# tutorial.net
KiCad netlist of a schematic drawn in Altium Designer
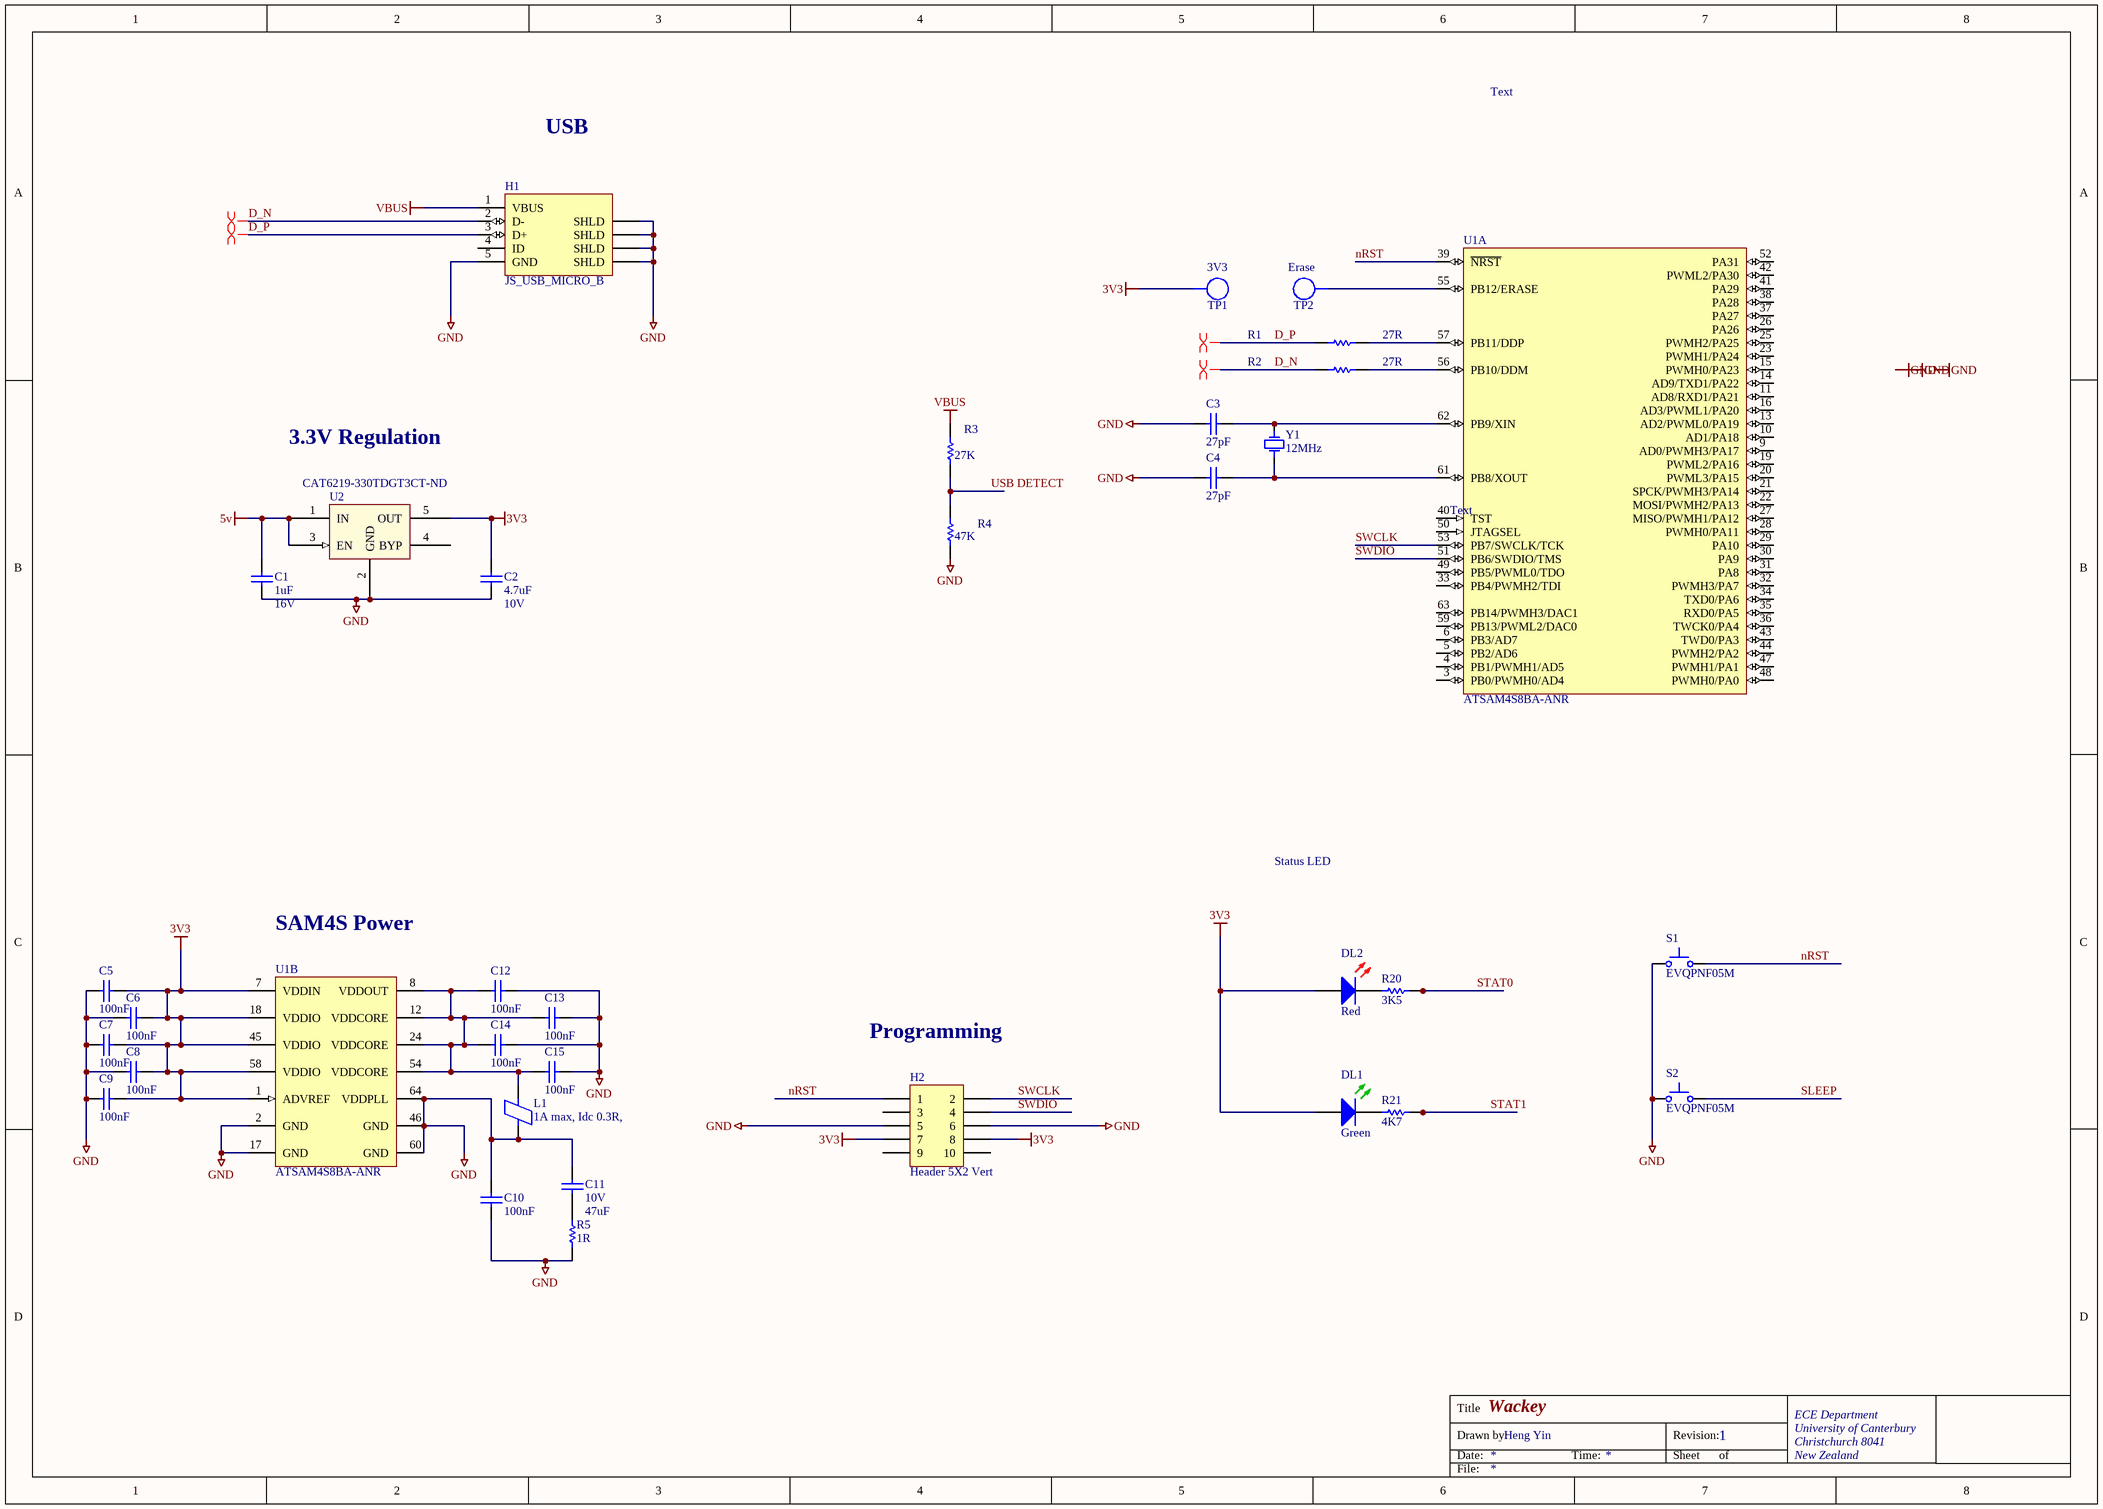
[diagram p0: tutorial.SchDoc]

(export (version "E")
  (design (tool "Eeschema 10.0.6"))
  (components
    (comp (ref "C1")
      (value "1uF")
      (footprint "CAPC1608L")
      (description "CAP CER 1uF Y5V -20% +80% 16V 0603")
      (fields (field (name "MAX VOLTAGE") "16V"))
      (libsource (lib "ECE AD19Components_22V1") (part "CC_1uF_0603"))
    )
    (comp (ref "C2")
      (value "4.7uF")
      (footprint "CAPC1608N")
      (description "CAP CER 4.7uF X5R +-20%  10V 0603")
      (fields (field (name "MAX VOLTAGE") "10V"))
      (libsource (lib "ECE AD19Components_22V1") (part "CC_4.7uF_0603"))
    )
    (comp (ref "C3")
      (value "27pF")
      (footprint "CAPC1608L")
      (description "CAP CER 27pF NPO/COG +-5% 50V 0603")
      (libsource (lib "ECE AD19Components_22V1") (part "CC_27pF_0603"))
    )
    (comp (ref "C4")
      (value "27pF")
      (footprint "CAPC1608L")
      (description "CAP CER 27pF NPO/COG +-5% 50V 0603")
      (libsource (lib "ECE AD19Components_22V1") (part "CC_27pF_0603"))
    )
    (comp (ref "C5")
      (value "100nF")
      (footprint "CAPC1608L")
      (description "CAP CER 100nF X7R +-10% 50V 0603")
      (libsource (lib "ECE AD19Components_22V1") (part "CC_100nF_0603"))
    )
    (comp (ref "C6")
      (value "100nF")
      (footprint "CAPC1608L")
      (description "CAP CER 100nF X7R +-10% 50V 0603")
      (libsource (lib "ECE AD19Components_22V1") (part "CC_100nF_0603"))
    )
    (comp (ref "C7")
      (value "100nF")
      (footprint "CAPC1608L")
      (description "CAP CER 100nF X7R +-10% 50V 0603")
      (libsource (lib "ECE AD19Components_22V1") (part "CC_100nF_0603"))
    )
    (comp (ref "C8")
      (value "100nF")
      (footprint "CAPC1608L")
      (description "CAP CER 100nF X7R +-10% 50V 0603")
      (libsource (lib "ECE AD19Components_22V1") (part "CC_100nF_0603"))
    )
    (comp (ref "C9")
      (value "100nF")
      (footprint "CAPC1608L")
      (description "CAP CER 100nF X7R +-10% 50V 0603")
      (libsource (lib "ECE AD19Components_22V1") (part "CC_100nF_0603"))
    )
    (comp (ref "C10")
      (value "100nF")
      (footprint "CAPC1608L")
      (description "CAP CER 100nF X7R +-10% 50V 0603")
      (libsource (lib "ECE AD19Components_22V1") (part "CC_100nF_0603"))
    )
    (comp (ref "C11")
      (value "47uF")
      (footprint "CAPC3216L")
      (description "CAP CER 47uF X5R -/+20% 10V 1206")
      (fields (field (name "MAX VOLTAGE") "10V"))
      (libsource (lib "ECE AD19Components_22V1") (part "CC_47uF_1206"))
    )
    (comp (ref "C12")
      (value "100nF")
      (footprint "CAPC1608L")
      (description "CAP CER 100nF X7R +-10% 50V 0603")
      (libsource (lib "ECE AD19Components_22V1") (part "CC_100nF_0603"))
    )
    (comp (ref "C13")
      (value "100nF")
      (footprint "CAPC1608L")
      (description "CAP CER 100nF X7R +-10% 50V 0603")
      (libsource (lib "ECE AD19Components_22V1") (part "CC_100nF_0603"))
    )
    (comp (ref "C14")
      (value "100nF")
      (footprint "CAPC1608L")
      (description "CAP CER 100nF X7R +-10% 50V 0603")
      (libsource (lib "ECE AD19Components_22V1") (part "CC_100nF_0603"))
    )
    (comp (ref "C15")
      (value "100nF")
      (footprint "CAPC1608L")
      (description "CAP CER 100nF X7R +-10% 50V 0603")
      (libsource (lib "ECE AD19Components_22V1") (part "CC_100nF_0603"))
    )
    (comp (ref "DL1")
      (value "Green")
      (footprint "WL-SMCW0603")
      (description "LED Green 430mcd 0603 SMD")
      (fields
        (field (name "MANUFACTURER") "WURTH ELEKTRONIK")
        (field (name "MANUFACTURER PART NUMBER") "150060GS75000")
        (field (name "LED COLOUR") "Green")
      )
      (libsource (lib "ECE AD19Components_22V1") (part "DL_150060GS75000"))
    )
    (comp (ref "DL2")
      (value "Red")
      (footprint "WL-SMCW0603")
      (description "LED Red 250mcd 0603 SMD")
      (fields
        (field (name "MANUFACTURER") "WURTH ELEKTRONIK")
        (field (name "MANUFACTURER PART NUMBER") "150060RS75000")
        (field (name "LED COLOUR") "Red")
      )
      (libsource (lib "ECE AD19Components_22V1") (part "DL_150060RS75000"))
    )
    (comp (ref "H1")
      (value "JS_USB_MICRO_B")
      (footprint "FCI_USB_10118194-0001LF")
      (description "CONN USB MICRO B RECPT SMT R/A")
      (fields (field (name "MANUFACTURER") "FCI") (field (name "MANUFACTURER PART NUMBER") "10118194-0001LF"))
      (libsource (lib "ECE AD19Components_22V1") (part "JS_USB_MICRO_B_SMT"))
    )
    (comp (ref "H2")
      (value "Header 5X2 Vert")
      (footprint "IDC2.54-V10D")
      (description "IDC Header, 2,54mm, 10-Pin, Vert")
      (libsource (lib "ECE AD19Components_22V1") (part "JA_HDR_IDC_5X2_VERT"))
    )
    (comp (ref "L1")
      (value "1A max, Idc 0.3R,")
      (footprint "INDC3216L")
      (description "Ferrite Bead, Rdc 0.3R, Z100MHZ 600R, Imax 1A, SMD 1206")
      (fields
        (field (name "MANUFACTURER") "FAIR-RITE")
        (field (name "MANUFACTURER PART NUMBER") "2512066017Y1")
      )
      (libsource (lib "ECE AD19Components_22V1") (part "IN_Ferrite-Bead"))
    )
    (comp (ref "R1")
      (value "27R")
      (footprint "RESC1608L")
      (description "RES 27 OHM 1/10W 5% 0603 SMD")
      (libsource (lib "ECE AD19Components_22V1") (part "RS_27R"))
    )
    (comp (ref "R2")
      (value "27R")
      (footprint "RESC1608L")
      (description "RES 27 OHM 1/10W 5% 0603 SMD")
      (libsource (lib "ECE AD19Components_22V1") (part "RS_27R"))
    )
    (comp (ref "R3")
      (value "27K")
      (footprint "RESC1608L")
      (description "RES 27K OHM 1/10W 5% 0603 SMD")
      (libsource (lib "ECE AD19Components_22V1") (part "RS_27K"))
    )
    (comp (ref "R4")
      (value "47K")
      (footprint "RESC1608N")
      (description "RES 47.0K OHM 1/10W 5% 0603 SMD")
      (libsource (lib "ECE AD19Components_22V1") (part "RS_47K"))
    )
    (comp (ref "R5")
      (value "1R")
      (footprint "RESC3216L")
      (description "RES 1R OHM 1/4W 5% 1206 SMD")
      (libsource (lib "ECE AD19Components_22V1") (part "RT_1R"))
    )
    (comp (ref "R20")
      (value "3K5")
      (footprint "RESC1608L")
      (description "RES 4.7K OHM 1/10W 5% 0603 SMD")
      (libsource (lib "ECE AD19Components_22V1") (part "RS_4K7"))
    )
    (comp (ref "R21")
      (value "4K7")
      (footprint "RESC1608L")
      (description "RES 4.7K OHM 1/10W 5% 0603 SMD")
      (libsource (lib "ECE AD19Components_22V1") (part "RS_4K7"))
    )
    (comp (ref "S1")
      (value "EVQPNF05M")
      (footprint "EVQPNF05M")
      (description "Panasonic 6 x 3.5mm SMD Light Touch Switch Type SMD")
      (fields (field (name "MANUFACTURER") "Panasonic"))
      (libsource (lib "ECE AD19Components_22V1") (part "WS_EVQPNF05M"))
    )
    (comp (ref "S2")
      (value "EVQPNF05M")
      (footprint "EVQPNF05M")
      (description "Panasonic 6 x 3.5mm SMD Light Touch Switch Type SMD")
      (fields (field (name "MANUFACTURER") "Panasonic"))
      (libsource (lib "ECE AD19Components_22V1") (part "WS_EVQPNF05M"))
    )
    (comp (ref "TP1")
      (value "TP")
      (footprint "TP_1206")
      (description "Test-Point 3.3x1.6x2.1mm SMD")
      (fields
        (field (name "MANUFACTURER") "Harwin Inc")
        (field (name "MANUFACTURER PART NUMBER") "S1751-46R")
      )
      (libsource (lib "ECE AD19Components_22V1") (part "TP_1206"))
    )
    (comp (ref "TP2")
      (value "TP")
      (footprint "TP_1206")
      (description "Test-Point 3.3x1.6x2.1mm SMD")
      (fields
        (field (name "MANUFACTURER") "Harwin Inc")
        (field (name "MANUFACTURER PART NUMBER") "S1751-46R")
      )
      (libsource (lib "ECE AD19Components_22V1") (part "TP_1206"))
    )
    (comp (ref "U1")
      (value "ATSAM4S8BA-ANR")
      (footprint "LQFP64_L")
      (description "IC MCU 32BIT 512KB FLASH 64LQFP")
      (fields (field (name "MANUFACTURER") "Atmel"))
      (libsource (lib "ECE AD19Components_22V1") (part "SE_ATSAM4S16BA-MU"))
    )
    (comp (ref "U2")
      (value "CAT6219-330TDGT3")
      (footprint "SOT95P280X145-5N")
      (description "IC REG LIN 3.3V 500MA TSOT23-5")
      (fields
        (field (name "BASE PART NUMBER") "CAT6219")
        (field (name "SUPPLIER PART NUMBER") "CAT6219-330TDGT3CT-ND")
      )
      (libsource (lib "ENCE461AD19_V23") (part "SV_CAT6219-330TDGT3"))
    )
    (comp (ref "Y1")
      (value "12MHz")
      (footprint "6.0X3.5-4")
      (description "CRYSTAL 12MHZ 18PF 6X3.5mm SMD")
      (fields
        (field (name "MANUFACTURER") "CTS-Frequency Controls")
        (field (name "MANUFACTURER PART NUMBER") "406C35D12M00000")
        (field (name "FREQUENCY") "12MHz")
      )
      (libsource (lib "ECE AD19Components_22V1") (part "XT_CRYSTAL_12MHz_18pF"))
    )
  )
  (nets
    (net (code "1") (name "/D_N") (class "Default")
      (node (ref "H1") (pin "2") (pinfunction "D-_2") (pintype "bidirectional"))
      (node (ref "R2") (pin "1") (pinfunction "1_1") (pintype "passive"))
    )
    (net (code "2") (name "/D_P") (class "Default")
      (node (ref "H1") (pin "3") (pinfunction "D+_3") (pintype "bidirectional"))
      (node (ref "R1") (pin "1") (pinfunction "1_1") (pintype "passive"))
    )
    (net (code "3") (name "/SLEEP") (class "Default") (node (ref "S2") (pin "2") (pintype "passive")))
    (net (code "4") (name "/STAT0") (class "Default")
      (node (ref "R20") (pin "2") (pinfunction "2_2") (pintype "passive"))
    )
    (net (code "5") (name "/STAT1") (class "Default")
      (node (ref "R21") (pin "2") (pinfunction "2_2") (pintype "passive"))
    )
    (net (code "6") (name "/SWCLK") (class "Default")
      (node (ref "H2") (pin "2") (pinfunction "2_2") (pintype "passive"))
      (node (ref "U1") (pin "53") (pinfunction "PB7/SWCLK/TCK_53") (pintype "bidirectional"))
    )
    (net (code "7") (name "/SWDIO") (class "Default")
      (node (ref "H2") (pin "4") (pinfunction "4_4") (pintype "passive"))
      (node (ref "U1") (pin "51") (pinfunction "PB6/SWDIO/TMS_51") (pintype "bidirectional"))
    )
    (net (code "8") (name "/USB DETECT") (class "Default")
      (node (ref "R3") (pin "1") (pinfunction "1_1") (pintype "passive"))
      (node (ref "R4") (pin "2") (pinfunction "2_2") (pintype "passive"))
    )
    (net (code "9") (name "/nRST") (class "Default")
      (node (ref "H2") (pin "1") (pinfunction "1_1") (pintype "passive"))
      (node (ref "S1") (pin "2") (pintype "passive"))
      (node (ref "U1") (pin "39") (pinfunction "~{NRST}_39") (pintype "bidirectional"))
    )
    (net (code "10") (name "3V3") (class "Default")
      (node (ref "C2") (pin "2") (pinfunction "2_2") (pintype "passive"))
      (node (ref "C5") (pin "2") (pinfunction "2_2") (pintype "passive"))
      (node (ref "C6") (pin "2") (pinfunction "2_2") (pintype "passive"))
      (node (ref "C7") (pin "2") (pinfunction "2_2") (pintype "passive"))
      (node (ref "C8") (pin "2") (pinfunction "2_2") (pintype "passive"))
      (node (ref "C9") (pin "1") (pinfunction "1_1") (pintype "passive"))
      (node (ref "DL1") (pin "2") (pinfunction "A_2") (pintype "passive"))
      (node (ref "DL2") (pin "2") (pinfunction "A_2") (pintype "passive"))
      (node (ref "H2") (pin "7") (pinfunction "7_7") (pintype "passive"))
      (node (ref "H2") (pin "8") (pinfunction "8_8") (pintype "passive"))
      (node (ref "TP1") (pin "1") (pinfunction "1_1") (pintype "passive"))
      (node (ref "U1") (pin "1") (pinfunction "ADVREF_1") (pintype "input"))
      (node (ref "U1") (pin "18") (pinfunction "VDDIO_18") (pintype "power_in"))
      (node (ref "U1") (pin "45") (pinfunction "VDDIO_45") (pintype "power_in"))
      (node (ref "U1") (pin "58") (pinfunction "VDDIO_58") (pintype "power_in"))
      (node (ref "U1") (pin "7") (pinfunction "VDDIN_7") (pintype "power_in"))
      (node (ref "U2") (pin "5") (pinfunction "OUT_5") (pintype "power_in"))
    )
    (net (code "11") (name "5v") (class "Default")
      (node (ref "C1") (pin "2") (pinfunction "2_2") (pintype "passive"))
      (node (ref "U2") (pin "1") (pinfunction "IN_1") (pintype "power_in"))
      (node (ref "U2") (pin "3") (pinfunction "EN_3") (pintype "input"))
    )
    (net (code "12") (name "GND") (class "Default")
      (node (ref "C1") (pin "1") (pinfunction "1_1") (pintype "passive"))
      (node (ref "C10") (pin "1") (pinfunction "1_1") (pintype "passive"))
      (node (ref "C10") (pin "2") (pinfunction "2_2") (pintype "passive"))
      (node (ref "C11") (pin "2") (pinfunction "2_2") (pintype "passive"))
      (node (ref "C12") (pin "2") (pinfunction "2_2") (pintype "passive"))
      (node (ref "C13") (pin "2") (pinfunction "2_2") (pintype "passive"))
      (node (ref "C14") (pin "2") (pinfunction "2_2") (pintype "passive"))
      (node (ref "C15") (pin "2") (pinfunction "2_2") (pintype "passive"))
      (node (ref "C2") (pin "1") (pinfunction "1_1") (pintype "passive"))
      (node (ref "C3") (pin "1") (pinfunction "1_1") (pintype "passive"))
      (node (ref "C4") (pin "1") (pinfunction "1_1") (pintype "passive"))
      (node (ref "C5") (pin "1") (pinfunction "1_1") (pintype "passive"))
      (node (ref "C6") (pin "1") (pinfunction "1_1") (pintype "passive"))
      (node (ref "C7") (pin "1") (pinfunction "1_1") (pintype "passive"))
      (node (ref "C8") (pin "1") (pinfunction "1_1") (pintype "passive"))
      (node (ref "C9") (pin "2") (pinfunction "2_2") (pintype "passive"))
      (node (ref "H1") (pin "5") (pinfunction "GND_5") (pintype "passive"))
      (node (ref "H1") (pin "6") (pinfunction "SHLD_6") (pintype "passive"))
      (node (ref "H2") (pin "5") (pinfunction "5_5") (pintype "passive"))
      (node (ref "H2") (pin "6") (pinfunction "6_6") (pintype "passive"))
      (node (ref "L1") (pin "1") (pinfunction "1_1") (pintype "passive"))
      (node (ref "R4") (pin "1") (pinfunction "1_1") (pintype "passive"))
      (node (ref "R5") (pin "1") (pinfunction "1_1") (pintype "passive"))
      (node (ref "S1") (pin "1") (pintype "passive"))
      (node (ref "S2") (pin "1") (pintype "passive"))
      (node (ref "U1") (pin "17") (pinfunction "GND_17") (pintype "power_in"))
      (node (ref "U1") (pin "2") (pinfunction "GND_2") (pintype "power_in"))
      (node (ref "U1") (pin "46") (pinfunction "GND_46") (pintype "power_in"))
      (node (ref "U1") (pin "60") (pinfunction "GND_60") (pintype "power_in"))
      (node (ref "U1") (pin "64") (pinfunction "VDDPLL_64") (pintype "power_in"))
      (node (ref "U2") (pin "2") (pinfunction "GND_2") (pintype "power_in"))
    )
    (net (code "13") (name "Net-(C11-Pad1)") (class "Default")
      (node (ref "C11") (pin "1") (pinfunction "1_1") (pintype "passive"))
      (node (ref "R5") (pin "2") (pinfunction "2_2") (pintype "passive"))
    )
    (net (code "14") (name "Net-(U1A-PB8{slash}XOUT)") (class "Default")
      (node (ref "C4") (pin "2") (pinfunction "2_2") (pintype "passive"))
      (node (ref "U1") (pin "61") (pinfunction "PB8/XOUT_61") (pintype "bidirectional"))
      (node (ref "Y1") (pin "1") (pinfunction "OSC1_1") (pintype "passive"))
    )
    (net (code "15") (name "Net-(U1A-PB9{slash}XIN)") (class "Default")
      (node (ref "C3") (pin "2") (pinfunction "2_2") (pintype "passive"))
      (node (ref "U1") (pin "62") (pinfunction "PB9/XIN_62") (pintype "bidirectional"))
      (node (ref "Y1") (pin "3") (pinfunction "OSC2_3") (pintype "passive"))
    )
    (net (code "16") (name "Net-(U1A-PB10{slash}DDM)") (class "Default")
      (node (ref "R2") (pin "2") (pinfunction "2_2") (pintype "passive"))
      (node (ref "U1") (pin "56") (pinfunction "PB10/DDM_56") (pintype "bidirectional"))
    )
    (net (code "17") (name "Net-(U1A-PB11{slash}DDP)") (class "Default")
      (node (ref "R1") (pin "2") (pinfunction "2_2") (pintype "passive"))
      (node (ref "U1") (pin "57") (pinfunction "PB11/DDP_57") (pintype "bidirectional"))
    )
    (net (code "18") (name "Net-(U1A-PB12{slash}ERASE)") (class "Default")
      (node (ref "TP2") (pin "1") (pinfunction "1_1") (pintype "passive"))
      (node (ref "U1") (pin "55") (pinfunction "PB12/ERASE_55") (pintype "bidirectional"))
    )
    (net (code "19") (name "Net-(U1B-VDDOUT)") (class "Default")
      (node (ref "C12") (pin "1") (pinfunction "1_1") (pintype "passive"))
      (node (ref "C13") (pin "1") (pinfunction "1_1") (pintype "passive"))
      (node (ref "C14") (pin "1") (pinfunction "1_1") (pintype "passive"))
      (node (ref "C15") (pin "1") (pinfunction "1_1") (pintype "passive"))
      (node (ref "L1") (pin "2") (pinfunction "2_2") (pintype "passive"))
      (node (ref "U1") (pin "12") (pinfunction "VDDCORE_12") (pintype "power_in"))
      (node (ref "U1") (pin "24") (pinfunction "VDDCORE_24") (pintype "power_in"))
      (node (ref "U1") (pin "54") (pinfunction "VDDCORE_54") (pintype "power_in"))
      (node (ref "U1") (pin "8") (pinfunction "VDDOUT_8") (pintype "power_in"))
    )
    (net (code "20") (name "VBUS") (class "Default")
      (node (ref "H1") (pin "1") (pinfunction "VBUS_1") (pintype "power_in"))
      (node (ref "R3") (pin "2") (pinfunction "2_2") (pintype "passive"))
    )
    (net (code "21") (name "unconnected-(DL1-K-Pad1)") (class "Default")
      (node (ref "DL1") (pin "1") (pinfunction "K_1") (pintype "passive"))
    )
    (net (code "22") (name "unconnected-(DL2-K-Pad1)") (class "Default")
      (node (ref "DL2") (pin "1") (pinfunction "K_1") (pintype "passive"))
    )
    (net (code "23") (name "unconnected-(H1-ID-Pad4)") (class "Default")
      (node (ref "H1") (pin "4") (pinfunction "ID_4") (pintype "power_in"))
    )
    (net (code "24") (name "unconnected-(H2-Pad3)") (class "Default")
      (node (ref "H2") (pin "3") (pinfunction "3_3") (pintype "passive"))
    )
    (net (code "25") (name "unconnected-(H2-Pad9)") (class "Default")
      (node (ref "H2") (pin "9") (pinfunction "9_9") (pintype "passive"))
    )
    (net (code "26") (name "unconnected-(H2-Pad10)") (class "Default")
      (node (ref "H2") (pin "10") (pinfunction "10_10") (pintype "passive"))
    )
    (net (code "27") (name "unconnected-(R20-Pad1)") (class "Default")
      (node (ref "R20") (pin "1") (pinfunction "1_1") (pintype "passive"))
    )
    (net (code "28") (name "unconnected-(R21-Pad1)") (class "Default")
      (node (ref "R21") (pin "1") (pinfunction "1_1") (pintype "passive"))
    )
    (net (code "29") (name "unconnected-(U1A-AD0{slash}PWMH3{slash}PA17-Pad9)") (class "Default")
      (node (ref "U1") (pin "9") (pinfunction "AD0/PWMH3/PA17_9") (pintype "bidirectional"))
    )
    (net (code "30") (name "unconnected-(U1A-AD1{slash}PA18-Pad10)") (class "Default")
      (node (ref "U1") (pin "10") (pinfunction "AD1/PA18_10") (pintype "bidirectional"))
    )
    (net (code "31") (name "unconnected-(U1A-AD2{slash}PWML0{slash}PA19-Pad13)") (class "Default")
      (node (ref "U1") (pin "13") (pinfunction "AD2/PWML0/PA19_13") (pintype "bidirectional"))
    )
    (net (code "32") (name "unconnected-(U1A-AD3{slash}PWML1{slash}PA20-Pad16)") (class "Default")
      (node (ref "U1") (pin "16") (pinfunction "AD3/PWML1/PA20_16") (pintype "bidirectional"))
    )
    (net (code "33") (name "unconnected-(U1A-AD8{slash}RXD1{slash}PA21-Pad11)") (class "Default")
      (node (ref "U1") (pin "11") (pinfunction "AD8/RXD1/PA21_11") (pintype "bidirectional"))
    )
    (net (code "34") (name "unconnected-(U1A-AD9{slash}TXD1{slash}PA22-Pad14)") (class "Default")
      (node (ref "U1") (pin "14") (pinfunction "AD9/TXD1/PA22_14") (pintype "bidirectional"))
    )
    (net (code "35") (name "unconnected-(U1A-JTAGSEL-Pad50)") (class "Default")
      (node (ref "U1") (pin "50") (pinfunction "JTAGSEL_50") (pintype "input"))
    )
    (net (code "36") (name "unconnected-(U1A-MISO{slash}PWMH1{slash}PA12-Pad27)") (class "Default")
      (node (ref "U1") (pin "27") (pinfunction "MISO/PWMH1/PA12_27") (pintype "bidirectional"))
    )
    (net (code "37") (name "unconnected-(U1A-MOSI{slash}PWMH2{slash}PA13-Pad22)") (class "Default")
      (node (ref "U1") (pin "22") (pinfunction "MOSI/PWMH2/PA13_22") (pintype "bidirectional"))
    )
    (net (code "38") (name "unconnected-(U1A-PA8-Pad31)") (class "Default")
      (node (ref "U1") (pin "31") (pinfunction "PA8_31") (pintype "bidirectional"))
    )
    (net (code "39") (name "unconnected-(U1A-PA9-Pad30)") (class "Default")
      (node (ref "U1") (pin "30") (pinfunction "PA9_30") (pintype "bidirectional"))
    )
    (net (code "40") (name "unconnected-(U1A-PA10-Pad29)") (class "Default")
      (node (ref "U1") (pin "29") (pinfunction "PA10_29") (pintype "bidirectional"))
    )
    (net (code "41") (name "unconnected-(U1A-PA26-Pad26)") (class "Default")
      (node (ref "U1") (pin "26") (pinfunction "PA26_26") (pintype "bidirectional"))
    )
    (net (code "42") (name "unconnected-(U1A-PA27-Pad37)") (class "Default")
      (node (ref "U1") (pin "37") (pinfunction "PA27_37") (pintype "bidirectional"))
    )
    (net (code "43") (name "unconnected-(U1A-PA28-Pad38)") (class "Default")
      (node (ref "U1") (pin "38") (pinfunction "PA28_38") (pintype "bidirectional"))
    )
    (net (code "44") (name "unconnected-(U1A-PA29-Pad41)") (class "Default")
      (node (ref "U1") (pin "41") (pinfunction "PA29_41") (pintype "bidirectional"))
    )
    (net (code "45") (name "unconnected-(U1A-PA31-Pad52)") (class "Default")
      (node (ref "U1") (pin "52") (pinfunction "PA31_52") (pintype "bidirectional"))
    )
    (net (code "46") (name "unconnected-(U1A-PB0{slash}PWMH0{slash}AD4-Pad3)") (class "Default")
      (node (ref "U1") (pin "3") (pinfunction "PB0/PWMH0/AD4_3") (pintype "bidirectional"))
    )
    (net (code "47") (name "unconnected-(U1A-PB1{slash}PWMH1{slash}AD5-Pad4)") (class "Default")
      (node (ref "U1") (pin "4") (pinfunction "PB1/PWMH1/AD5_4") (pintype "bidirectional"))
    )
    (net (code "48") (name "unconnected-(U1A-PB2{slash}AD6-Pad5)") (class "Default")
      (node (ref "U1") (pin "5") (pinfunction "PB2/AD6_5") (pintype "bidirectional"))
    )
    (net (code "49") (name "unconnected-(U1A-PB3{slash}AD7-Pad6)") (class "Default")
      (node (ref "U1") (pin "6") (pinfunction "PB3/AD7_6") (pintype "bidirectional"))
    )
    (net (code "50") (name "unconnected-(U1A-PB4{slash}PWMH2{slash}TDI-Pad33)") (class "Default")
      (node (ref "U1") (pin "33") (pinfunction "PB4/PWMH2/TDI_33") (pintype "bidirectional"))
    )
    (net (code "51") (name "unconnected-(U1A-PB5{slash}PWML0{slash}TDO-Pad49)") (class "Default")
      (node (ref "U1") (pin "49") (pinfunction "PB5/PWML0/TDO_49") (pintype "bidirectional"))
    )
    (net (code "52") (name "unconnected-(U1A-PB13{slash}PWML2{slash}DAC0-Pad59)") (class "Default")
      (node (ref "U1") (pin "59") (pinfunction "PB13/PWML2/DAC0_59") (pintype "bidirectional"))
    )
    (net (code "53") (name "unconnected-(U1A-PB14{slash}PWMH3{slash}DAC1-Pad63)") (class "Default")
      (node (ref "U1") (pin "63") (pinfunction "PB14/PWMH3/DAC1_63") (pintype "bidirectional"))
    )
    (net (code "54") (name "unconnected-(U1A-PWMH0{slash}PA0-Pad48)") (class "Default")
      (node (ref "U1") (pin "48") (pinfunction "PWMH0/PA0_48") (pintype "bidirectional"))
    )
    (net (code "55") (name "unconnected-(U1A-PWMH0{slash}PA11-Pad28)") (class "Default")
      (node (ref "U1") (pin "28") (pinfunction "PWMH0/PA11_28") (pintype "bidirectional"))
    )
    (net (code "56") (name "unconnected-(U1A-PWMH0{slash}PA23-Pad15)") (class "Default")
      (node (ref "U1") (pin "15") (pinfunction "PWMH0/PA23_15") (pintype "bidirectional"))
    )
    (net (code "57") (name "unconnected-(U1A-PWMH1{slash}PA1-Pad47)") (class "Default")
      (node (ref "U1") (pin "47") (pinfunction "PWMH1/PA1_47") (pintype "bidirectional"))
    )
    (net (code "58") (name "unconnected-(U1A-PWMH1{slash}PA24-Pad23)") (class "Default")
      (node (ref "U1") (pin "23") (pinfunction "PWMH1/PA24_23") (pintype "bidirectional"))
    )
    (net (code "59") (name "unconnected-(U1A-PWMH2{slash}PA2-Pad44)") (class "Default")
      (node (ref "U1") (pin "44") (pinfunction "PWMH2/PA2_44") (pintype "bidirectional"))
    )
    (net (code "60") (name "unconnected-(U1A-PWMH2{slash}PA25-Pad25)") (class "Default")
      (node (ref "U1") (pin "25") (pinfunction "PWMH2/PA25_25") (pintype "bidirectional"))
    )
    (net (code "61") (name "unconnected-(U1A-PWMH3{slash}PA7-Pad32)") (class "Default")
      (node (ref "U1") (pin "32") (pinfunction "PWMH3/PA7_32") (pintype "bidirectional"))
    )
    (net (code "62") (name "unconnected-(U1A-PWML2{slash}PA16-Pad19)") (class "Default")
      (node (ref "U1") (pin "19") (pinfunction "PWML2/PA16_19") (pintype "bidirectional"))
    )
    (net (code "63") (name "unconnected-(U1A-PWML2{slash}PA30-Pad42)") (class "Default")
      (node (ref "U1") (pin "42") (pinfunction "PWML2/PA30_42") (pintype "bidirectional"))
    )
    (net (code "64") (name "unconnected-(U1A-PWML3{slash}PA15-Pad20)") (class "Default")
      (node (ref "U1") (pin "20") (pinfunction "PWML3/PA15_20") (pintype "bidirectional"))
    )
    (net (code "65") (name "unconnected-(U1A-RXD0{slash}PA5-Pad35)") (class "Default")
      (node (ref "U1") (pin "35") (pinfunction "RXD0/PA5_35") (pintype "bidirectional"))
    )
    (net (code "66") (name "unconnected-(U1A-SPCK{slash}PWMH3{slash}PA14-Pad21)") (class "Default")
      (node (ref "U1") (pin "21") (pinfunction "SPCK/PWMH3/PA14_21") (pintype "bidirectional"))
    )
    (net (code "67") (name "unconnected-(U1A-TST-Pad40)") (class "Default")
      (node (ref "U1") (pin "40") (pinfunction "TST_40") (pintype "input"))
    )
    (net (code "68") (name "unconnected-(U1A-TWCK0{slash}PA4-Pad36)") (class "Default")
      (node (ref "U1") (pin "36") (pinfunction "TWCK0/PA4_36") (pintype "bidirectional"))
    )
    (net (code "69") (name "unconnected-(U1A-TWD0{slash}PA3-Pad43)") (class "Default")
      (node (ref "U1") (pin "43") (pinfunction "TWD0/PA3_43") (pintype "bidirectional"))
    )
    (net (code "70") (name "unconnected-(U1A-TXD0{slash}PA6-Pad34)") (class "Default")
      (node (ref "U1") (pin "34") (pinfunction "TXD0/PA6_34") (pintype "bidirectional"))
    )
    (net (code "71") (name "unconnected-(U2-BYP-Pad4)") (class "Default")
      (node (ref "U2") (pin "4") (pinfunction "BYP_4") (pintype "passive"))
    )
  )
)
